# board.net
KiCad netlist of a schematic drawn in EAGLE
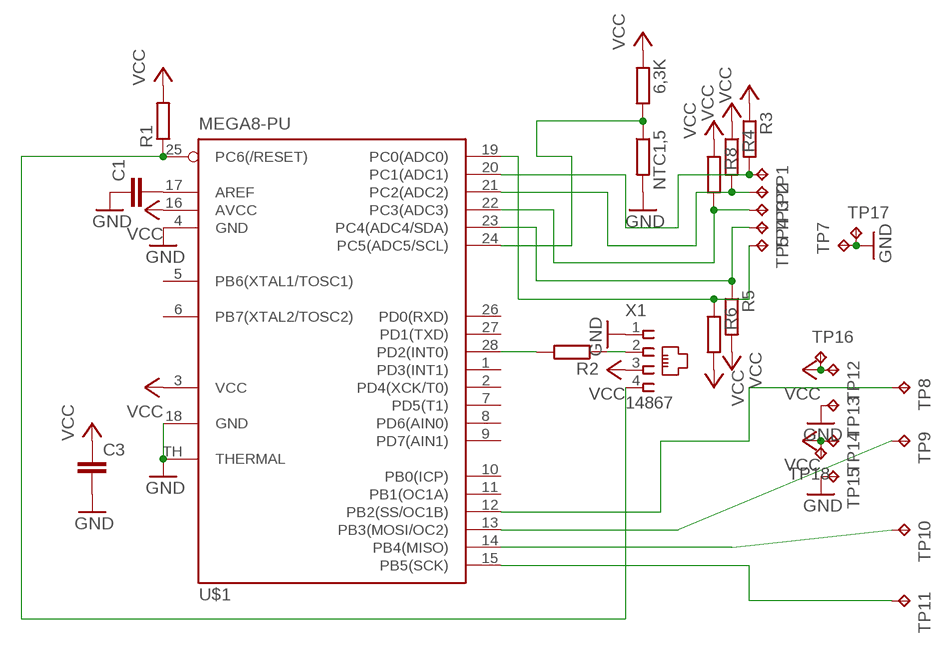
[diagram p0: schematic, sheet 1]

(export (version "E")
  (design (tool "Eeschema 10.0.6"))
  (components
    (comp (ref "6,3K")
      (value "R-EU_R0805")
      (footprint "eagle-import:R0805")
      (libsource (lib "eagle-import") (part "R-EU_R0805"))
    )
    (comp (ref "C1")
      (value "C-EUC0805")
      (footprint "eagle-import:C0805")
      (libsource (lib "eagle-import") (part "C-EUC0805"))
    )
    (comp (ref "C3")
      (value "C-EUC0805")
      (footprint "eagle-import:C0805")
      (libsource (lib "eagle-import") (part "C-EUC0805"))
    )
    (comp (ref "NTC1,5")
      (value "R-EU_0207/7")
      (footprint "eagle-import:0207_7")
      (libsource (lib "eagle-import") (part "R-EU_0207/7"))
    )
    (comp (ref "R1")
      (value "R-EU_R0805")
      (footprint "eagle-import:R0805")
      (libsource (lib "eagle-import") (part "R-EU_R0805"))
    )
    (comp (ref "R2")
      (value "R-EU_R0805")
      (footprint "eagle-import:R0805")
      (libsource (lib "eagle-import") (part "R-EU_R0805"))
    )
    (comp (ref "R3")
      (value "R-EU_R0805")
      (footprint "eagle-import:R0805")
      (libsource (lib "eagle-import") (part "R-EU_R0805"))
    )
    (comp (ref "R4")
      (value "R-EU_R0805")
      (footprint "eagle-import:R0805")
      (libsource (lib "eagle-import") (part "R-EU_R0805"))
    )
    (comp (ref "R5")
      (value "R-EU_R0805")
      (footprint "eagle-import:R0805")
      (libsource (lib "eagle-import") (part "R-EU_R0805"))
    )
    (comp (ref "R6")
      (value "R-EU_R0805")
      (footprint "eagle-import:R0805")
      (libsource (lib "eagle-import") (part "R-EU_R0805"))
    )
    (comp (ref "R8")
      (value "R-EU_R0805")
      (footprint "eagle-import:R0805")
      (libsource (lib "eagle-import") (part "R-EU_R0805"))
    )
    (comp (ref "TP1")
      (value "TPPAD1-13")
      (footprint "eagle-import:P1-13")
      (libsource (lib "eagle-import") (part "TPPAD1-13"))
    )
    (comp (ref "TP2")
      (value "TPPAD1-13")
      (footprint "eagle-import:P1-13")
      (libsource (lib "eagle-import") (part "TPPAD1-13"))
    )
    (comp (ref "TP3")
      (value "TPPAD1-13")
      (footprint "eagle-import:P1-13")
      (libsource (lib "eagle-import") (part "TPPAD1-13"))
    )
    (comp (ref "TP4")
      (value "TPPAD1-13")
      (footprint "eagle-import:P1-13")
      (libsource (lib "eagle-import") (part "TPPAD1-13"))
    )
    (comp (ref "TP5")
      (value "TPPAD1-13")
      (footprint "eagle-import:P1-13")
      (libsource (lib "eagle-import") (part "TPPAD1-13"))
    )
    (comp (ref "TP7")
      (value "TPPAD1-13")
      (footprint "eagle-import:P1-13")
      (libsource (lib "eagle-import") (part "TPPAD1-13"))
    )
    (comp (ref "TP8")
      (value "TPPAD1-13")
      (footprint "eagle-import:P1-13")
      (libsource (lib "eagle-import") (part "TPPAD1-13"))
    )
    (comp (ref "TP9")
      (value "TPPAD1-13")
      (footprint "eagle-import:P1-13")
      (libsource (lib "eagle-import") (part "TPPAD1-13"))
    )
    (comp (ref "TP10")
      (value "TPPAD1-13")
      (footprint "eagle-import:P1-13")
      (libsource (lib "eagle-import") (part "TPPAD1-13"))
    )
    (comp (ref "TP11")
      (value "TPPAD1-13")
      (footprint "eagle-import:P1-13")
      (libsource (lib "eagle-import") (part "TPPAD1-13"))
    )
    (comp (ref "TP12")
      (value "TPPAD1-13")
      (footprint "eagle-import:P1-13")
      (libsource (lib "eagle-import") (part "TPPAD1-13"))
    )
    (comp (ref "TP13")
      (value "TPPAD1-13")
      (footprint "eagle-import:P1-13")
      (libsource (lib "eagle-import") (part "TPPAD1-13"))
    )
    (comp (ref "TP14")
      (value "TPPAD1-13")
      (footprint "eagle-import:P1-13")
      (libsource (lib "eagle-import") (part "TPPAD1-13"))
    )
    (comp (ref "TP15")
      (value "TPPAD1-13")
      (footprint "eagle-import:P1-13")
      (libsource (lib "eagle-import") (part "TPPAD1-13"))
    )
    (comp (ref "TP16")
      (value "TPPAD1-13")
      (footprint "eagle-import:P1-13")
      (libsource (lib "eagle-import") (part "TPPAD1-13"))
    )
    (comp (ref "TP17")
      (value "TPPAD1-13")
      (footprint "eagle-import:P1-13")
      (libsource (lib "eagle-import") (part "TPPAD1-13"))
    )
    (comp (ref "TP18")
      (value "TPPAD1-13")
      (footprint "eagle-import:P1-13")
      (libsource (lib "eagle-import") (part "TPPAD1-13"))
    )
    (comp (ref "U$1")
      (value "MEGA8-PU")
      (footprint "eagle-import:MLF28-TH")
      (libsource (lib "eagle-import") (part "MEGA8-PU"))
    )
    (comp (ref "X1")
      (value "14867")
      (footprint "eagle-import:14867")
      (libsource (lib "eagle-import") (part "14867"))
    )
  )
  (nets
    (net (code "1") (name "GND") (class "Default")
      (node (ref "C1") (pin "1") (pinfunction "1_1") (pintype "passive"))
      (node (ref "C3") (pin "2") (pinfunction "2_2") (pintype "passive"))
      (node (ref "NTC1,5") (pin "2") (pinfunction "2_2") (pintype "passive"))
      (node (ref "TP13") (pin "TP") (pinfunction "TP_TP") (pintype "input"))
      (node (ref "TP15") (pin "TP") (pinfunction "TP_TP") (pintype "input"))
      (node (ref "TP17") (pin "TP") (pinfunction "TP_TP") (pintype "input"))
      (node (ref "TP7") (pin "TP") (pinfunction "TP_TP") (pintype "input"))
      (node (ref "U$1") (pin "18") (pinfunction "GND_18") (pintype "power_in"))
      (node (ref "U$1") (pin "4") (pinfunction "GND_4") (pintype "power_in"))
      (node (ref "U$1") (pin "TH") (pinfunction "THERMAL_TH") (pintype "power_in"))
      (node (ref "X1") (pin "1") (pinfunction "1_1") (pintype "passive"))
    )
    (net (code "2") (name "Net-(R2-Pad1)") (class "Default")
      (node (ref "R2") (pin "1") (pinfunction "1_1") (pintype "passive"))
      (node (ref "X1") (pin "2") (pinfunction "2_2") (pintype "passive"))
    )
    (net (code "3") (name "Net-(U$1-AREF)") (class "Default")
      (node (ref "C1") (pin "2") (pinfunction "2_2") (pintype "passive"))
      (node (ref "U$1") (pin "17") (pinfunction "AREF_17") (pintype "passive"))
    )
    (net (code "4") (name "Net-(U$1-PB2(SS{slash}OC1B))") (class "Default")
      (node (ref "TP8") (pin "TP") (pinfunction "TP_TP") (pintype "input"))
      (node (ref "U$1") (pin "12") (pinfunction "PB2(SS/OC1B)_12") (pintype "bidirectional"))
    )
    (net (code "5") (name "Net-(U$1-PB3(MOSI{slash}OC2))") (class "Default")
      (node (ref "TP9") (pin "TP") (pinfunction "TP_TP") (pintype "input"))
      (node (ref "U$1") (pin "13") (pinfunction "PB3(MOSI/OC2)_13") (pintype "bidirectional"))
    )
    (net (code "6") (name "Net-(U$1-PB4(MISO))") (class "Default")
      (node (ref "TP10") (pin "TP") (pinfunction "TP_TP") (pintype "input"))
      (node (ref "U$1") (pin "14") (pinfunction "PB4(MISO)_14") (pintype "bidirectional"))
    )
    (net (code "7") (name "Net-(U$1-PB5(SCK))") (class "Default")
      (node (ref "TP11") (pin "TP") (pinfunction "TP_TP") (pintype "input"))
      (node (ref "U$1") (pin "15") (pinfunction "PB5(SCK)_15") (pintype "bidirectional"))
    )
    (net (code "8") (name "Net-(U$1-PC0(ADC0))") (class "Default")
      (node (ref "R6") (pin "1") (pinfunction "1_1") (pintype "passive"))
      (node (ref "TP5") (pin "TP") (pinfunction "TP_TP") (pintype "input"))
      (node (ref "U$1") (pin "19") (pinfunction "PC0(ADC0)_19") (pintype "bidirectional"))
    )
    (net (code "9") (name "Net-(U$1-PC1(ADC1))") (class "Default")
      (node (ref "R3") (pin "2") (pinfunction "2_2") (pintype "passive"))
      (node (ref "TP1") (pin "TP") (pinfunction "TP_TP") (pintype "input"))
      (node (ref "U$1") (pin "20") (pinfunction "PC1(ADC1)_20") (pintype "bidirectional"))
    )
    (net (code "10") (name "Net-(U$1-PC2(ADC2))") (class "Default")
      (node (ref "R4") (pin "2") (pinfunction "2_2") (pintype "passive"))
      (node (ref "TP2") (pin "TP") (pinfunction "TP_TP") (pintype "input"))
      (node (ref "U$1") (pin "21") (pinfunction "PC2(ADC2)_21") (pintype "bidirectional"))
    )
    (net (code "11") (name "Net-(U$1-PC3(ADC3))") (class "Default")
      (node (ref "R8") (pin "2") (pinfunction "2_2") (pintype "passive"))
      (node (ref "TP3") (pin "TP") (pinfunction "TP_TP") (pintype "input"))
      (node (ref "U$1") (pin "22") (pinfunction "PC3(ADC3)_22") (pintype "bidirectional"))
    )
    (net (code "12") (name "Net-(U$1-PC4(ADC4{slash}SDA))") (class "Default")
      (node (ref "R5") (pin "1") (pinfunction "1_1") (pintype "passive"))
      (node (ref "TP4") (pin "TP") (pinfunction "TP_TP") (pintype "input"))
      (node (ref "U$1") (pin "23") (pinfunction "PC4(ADC4/SDA)_23") (pintype "bidirectional"))
    )
    (net (code "13") (name "Net-(U$1-PC5(ADC5{slash}SCL))") (class "Default")
      (node (ref "6,3K") (pin "2") (pinfunction "2_2") (pintype "passive"))
      (node (ref "NTC1,5") (pin "1") (pinfunction "1_1") (pintype "passive"))
      (node (ref "U$1") (pin "24") (pinfunction "PC5(ADC5/SCL)_24") (pintype "bidirectional"))
    )
    (net (code "14") (name "Net-(U$1-PC6({slash}RESET))") (class "Default")
      (node (ref "R1") (pin "1") (pinfunction "1_1") (pintype "passive"))
      (node (ref "U$1") (pin "25") (pinfunction "PC6(/RESET)_25") (pintype "bidirectional"))
      (node (ref "X1") (pin "4") (pinfunction "4_4") (pintype "passive"))
    )
    (net (code "15") (name "Net-(U$1-PD2(INT0))") (class "Default")
      (node (ref "R2") (pin "2") (pinfunction "2_2") (pintype "passive"))
      (node (ref "U$1") (pin "28") (pinfunction "PD2(INT0)_28") (pintype "bidirectional"))
    )
    (net (code "16") (name "VCC") (class "Default")
      (node (ref "6,3K") (pin "1") (pinfunction "1_1") (pintype "passive"))
      (node (ref "C3") (pin "1") (pinfunction "1_1") (pintype "passive"))
      (node (ref "R1") (pin "2") (pinfunction "2_2") (pintype "passive"))
      (node (ref "R3") (pin "1") (pinfunction "1_1") (pintype "passive"))
      (node (ref "R4") (pin "1") (pinfunction "1_1") (pintype "passive"))
      (node (ref "R5") (pin "2") (pinfunction "2_2") (pintype "passive"))
      (node (ref "R6") (pin "2") (pinfunction "2_2") (pintype "passive"))
      (node (ref "R8") (pin "1") (pinfunction "1_1") (pintype "passive"))
      (node (ref "TP12") (pin "TP") (pinfunction "TP_TP") (pintype "input"))
      (node (ref "TP14") (pin "TP") (pinfunction "TP_TP") (pintype "input"))
      (node (ref "TP16") (pin "TP") (pinfunction "TP_TP") (pintype "input"))
      (node (ref "TP18") (pin "TP") (pinfunction "TP_TP") (pintype "input"))
      (node (ref "U$1") (pin "16") (pinfunction "AVCC_16") (pintype "power_in"))
      (node (ref "U$1") (pin "3") (pinfunction "VCC_3") (pintype "power_in"))
      (node (ref "X1") (pin "3") (pinfunction "3_3") (pintype "passive"))
    )
    (net (code "17") (name "unconnected-(U$1-PB0(ICP)-Pad10)") (class "Default")
      (node (ref "U$1") (pin "10") (pinfunction "PB0(ICP)_10") (pintype "bidirectional"))
    )
    (net (code "18") (name "unconnected-(U$1-PB1(OC1A)-Pad11)") (class "Default")
      (node (ref "U$1") (pin "11") (pinfunction "PB1(OC1A)_11") (pintype "bidirectional"))
    )
    (net (code "19") (name "unconnected-(U$1-PB6(XTAL1{slash}TOSC1)-Pad5)") (class "Default")
      (node (ref "U$1") (pin "5") (pinfunction "PB6(XTAL1/TOSC1)_5") (pintype "bidirectional"))
    )
    (net (code "20") (name "unconnected-(U$1-PB7(XTAL2{slash}TOSC2)-Pad6)") (class "Default")
      (node (ref "U$1") (pin "6") (pinfunction "PB7(XTAL2/TOSC2)_6") (pintype "bidirectional"))
    )
    (net (code "21") (name "unconnected-(U$1-PD0(RXD)-Pad26)") (class "Default")
      (node (ref "U$1") (pin "26") (pinfunction "PD0(RXD)_26") (pintype "bidirectional"))
    )
    (net (code "22") (name "unconnected-(U$1-PD1(TXD)-Pad27)") (class "Default")
      (node (ref "U$1") (pin "27") (pinfunction "PD1(TXD)_27") (pintype "bidirectional"))
    )
    (net (code "23") (name "unconnected-(U$1-PD3(INT1)-Pad1)") (class "Default")
      (node (ref "U$1") (pin "1") (pinfunction "PD3(INT1)_1") (pintype "bidirectional"))
    )
    (net (code "24") (name "unconnected-(U$1-PD4(XCK{slash}T0)-Pad2)") (class "Default")
      (node (ref "U$1") (pin "2") (pinfunction "PD4(XCK/T0)_2") (pintype "bidirectional"))
    )
    (net (code "25") (name "unconnected-(U$1-PD5(T1)-Pad7)") (class "Default")
      (node (ref "U$1") (pin "7") (pinfunction "PD5(T1)_7") (pintype "bidirectional"))
    )
    (net (code "26") (name "unconnected-(U$1-PD6(AIN0)-Pad8)") (class "Default")
      (node (ref "U$1") (pin "8") (pinfunction "PD6(AIN0)_8") (pintype "bidirectional"))
    )
    (net (code "27") (name "unconnected-(U$1-PD7(AIN1)-Pad9)") (class "Default")
      (node (ref "U$1") (pin "9") (pinfunction "PD7(AIN1)_9") (pintype "bidirectional"))
    )
  )
)
